# template_25x45_5V.net
KiCad netlist of a schematic drawn in EAGLE
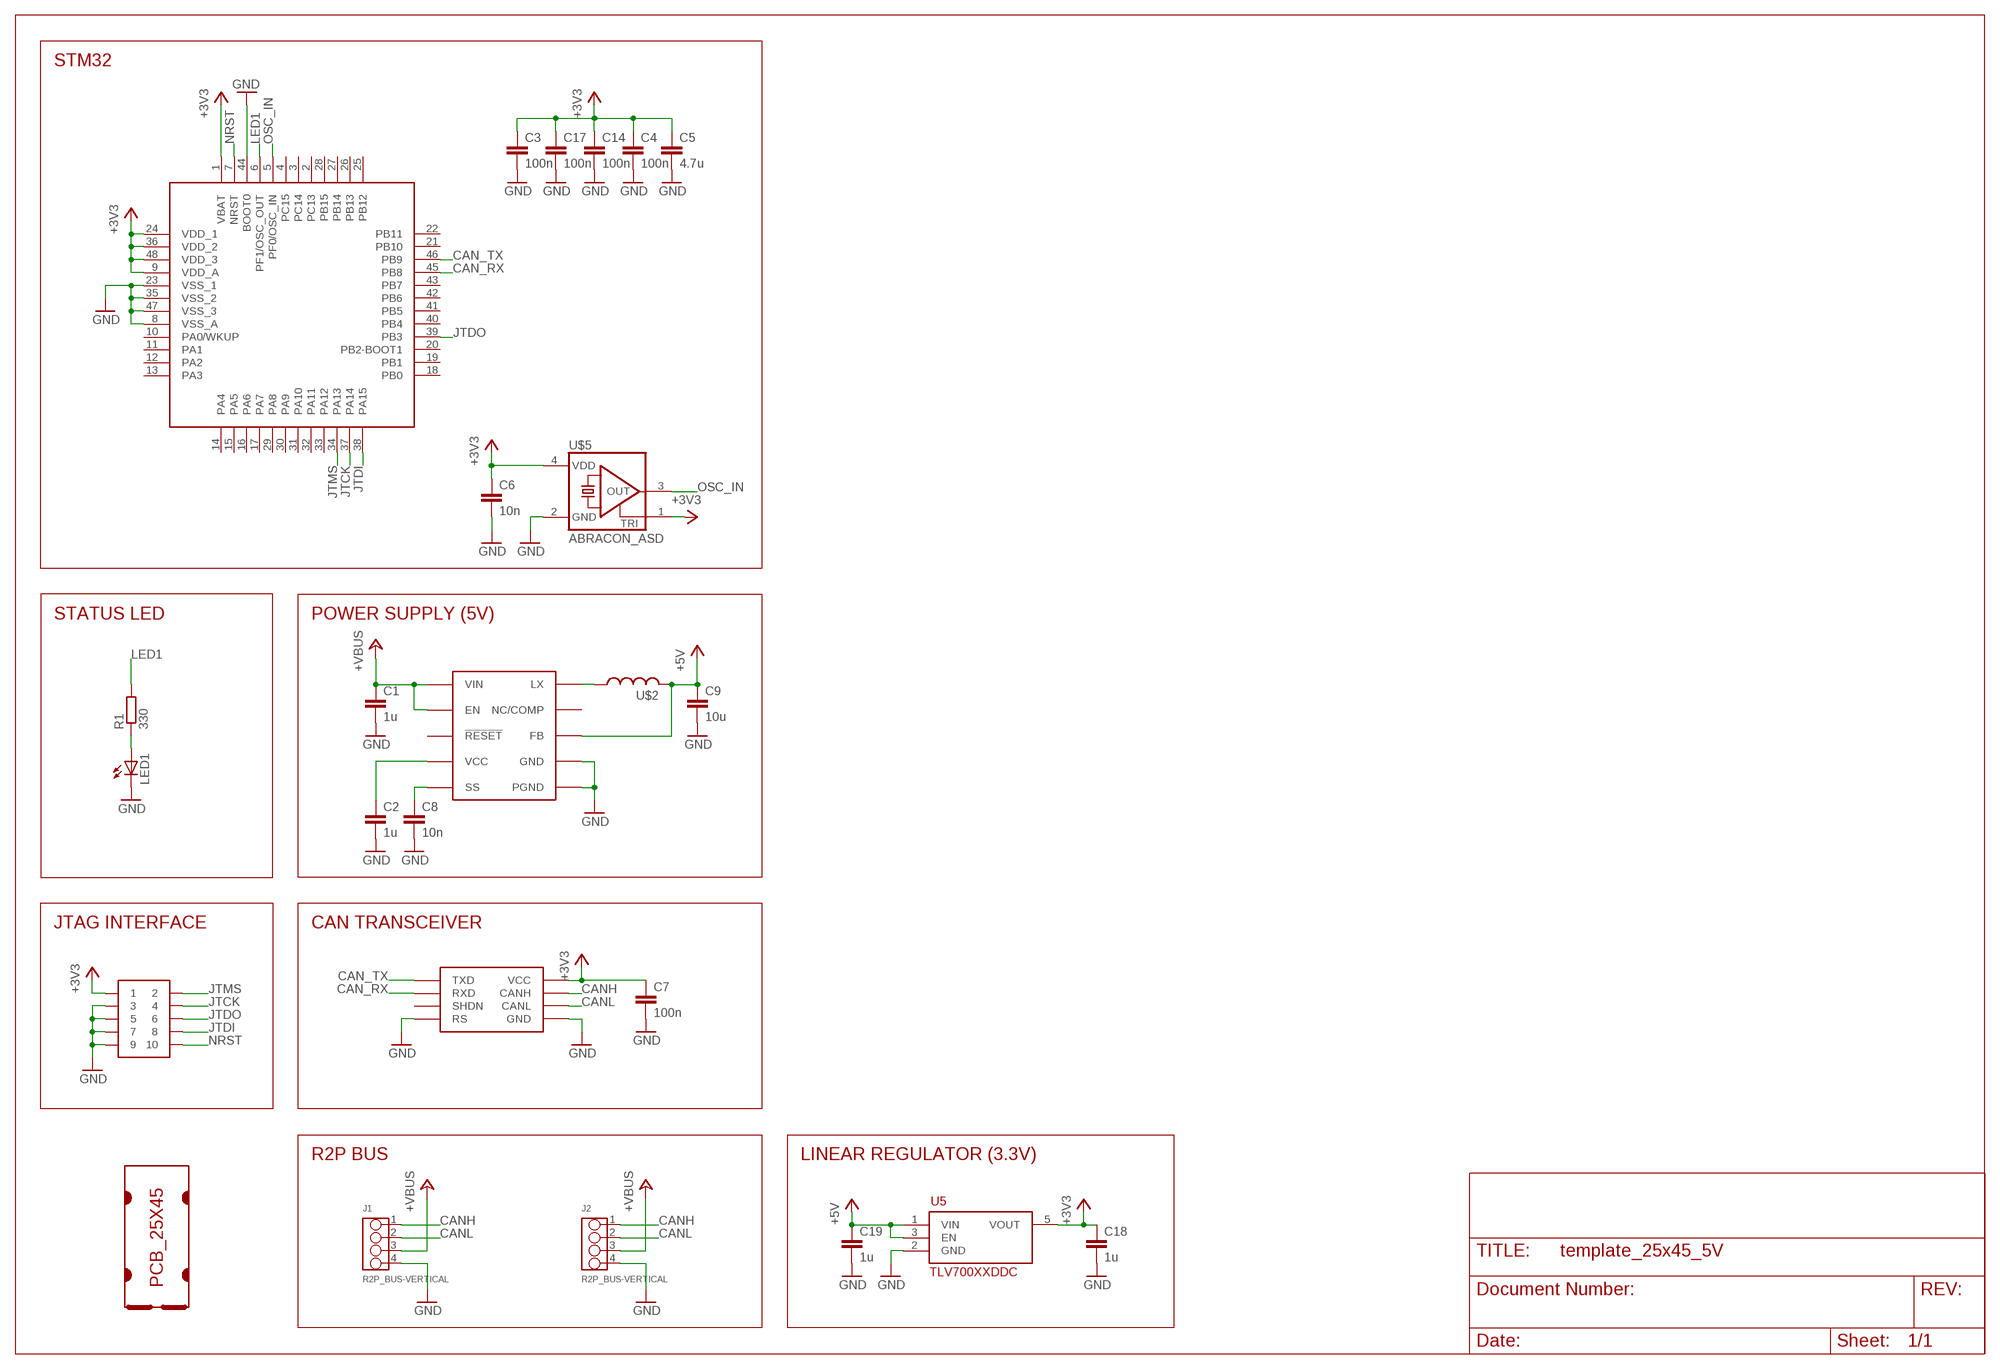
[diagram p0: schematic, sheet 1]

(export (version "E")
  (design (tool "Eeschema 10.0.6"))
  (components
    (comp (ref "C1")
      (value "1u")
      (footprint "eagle-import:C1206")
      (libsource (lib "eagle-import") (part "C1206"))
    )
    (comp (ref "C2")
      (value "1u")
      (footprint "eagle-import:C0603")
      (libsource (lib "eagle-import") (part "C0603"))
    )
    (comp (ref "C3")
      (value "100n")
      (footprint "eagle-import:C0603")
      (libsource (lib "eagle-import") (part "C0603"))
    )
    (comp (ref "C4")
      (value "100n")
      (footprint "eagle-import:C0603")
      (libsource (lib "eagle-import") (part "C0603"))
    )
    (comp (ref "C5")
      (value "4.7u")
      (footprint "eagle-import:C0805")
      (libsource (lib "eagle-import") (part "C0805"))
    )
    (comp (ref "C6")
      (value "10n")
      (footprint "eagle-import:C0603")
      (libsource (lib "eagle-import") (part "C0603"))
    )
    (comp (ref "C7")
      (value "100n")
      (footprint "eagle-import:C0603")
      (libsource (lib "eagle-import") (part "C0603"))
    )
    (comp (ref "C8")
      (value "10n")
      (footprint "eagle-import:C0603")
      (libsource (lib "eagle-import") (part "C0603"))
    )
    (comp (ref "C9")
      (value "10u")
      (footprint "eagle-import:C0805")
      (libsource (lib "eagle-import") (part "C0805"))
    )
    (comp (ref "C14")
      (value "100n")
      (footprint "eagle-import:C0603")
      (libsource (lib "eagle-import") (part "C0603"))
    )
    (comp (ref "C17")
      (value "100n")
      (footprint "eagle-import:C0603")
      (libsource (lib "eagle-import") (part "C0603"))
    )
    (comp (ref "C18")
      (value "1u")
      (footprint "eagle-import:C0603")
      (libsource (lib "eagle-import") (part "C0603"))
    )
    (comp (ref "C19")
      (value "1u")
      (footprint "eagle-import:C0603")
      (libsource (lib "eagle-import") (part "C0603"))
    )
    (comp (ref "J1")
      (value "R2P_BUS-VERTICAL")
      (footprint "eagle-import:OPL-EAGLE-LIBRARY_4P-2.0")
      (libsource (lib "eagle-import") (part "R2P_BUS-VERTICAL"))
    )
    (comp (ref "J2")
      (value "R2P_BUS-VERTICAL")
      (footprint "eagle-import:OPL-EAGLE-LIBRARY_4P-2.0")
      (libsource (lib "eagle-import") (part "R2P_BUS-VERTICAL"))
    )
    (comp (ref "LED1")
      (value "LED0805")
      (footprint "eagle-import:CHIPLED_0805")
      (libsource (lib "eagle-import") (part "LED0805"))
    )
    (comp (ref "R1")
      (value "330")
      (footprint "eagle-import:R0603")
      (libsource (lib "eagle-import") (part "R0603"))
    )
    (comp (ref "SOT1")
      (value "MAX3051EKA")
      (footprint "eagle-import:SOT23-8L")
      (libsource (lib "eagle-import") (part "MAX3051EKA"))
    )
    (comp (ref "U$1")
      (value "PCB_25X45")
      (footprint "eagle-import:25X45")
      (libsource (lib "eagle-import") (part "PCB_25X45"))
    )
    (comp (ref "U$2")
      (value "LPS4018")
      (footprint "eagle-import:COILCRAFT_LPS4018")
      (libsource (lib "eagle-import") (part "LPS4018"))
    )
    (comp (ref "U$3")
      (value "MAX17501")
      (footprint "eagle-import:TDFN-10")
      (libsource (lib "eagle-import") (part "MAX17501"))
    )
    (comp (ref "U$4")
      (value "JTAG-TH")
      (footprint "eagle-import:SAMTEC_FTSH-105-TH")
      (libsource (lib "eagle-import") (part "JTAG-TH"))
    )
    (comp (ref "U$5")
      (value "ABRACON_ASD")
      (footprint "eagle-import:ABRACON_2.5X2")
      (libsource (lib "eagle-import") (part "ABRACON_ASD"))
    )
    (comp (ref "U$6")
      (value "STM32F303CTX")
      (footprint "eagle-import:LQFP48")
      (libsource (lib "eagle-import") (part "STM32F303CTX"))
    )
    (comp (ref "U5")
      (value "TLV700XXDDC")
      (footprint "eagle-import:SOT23-5L")
      (libsource (lib "eagle-import") (part "TLV700XXDDC"))
    )
  )
  (nets
    (net (code "1") (name "+3V3") (class "Default")
      (node (ref "C14") (pin "1") (pinfunction "1_1") (pintype "passive"))
      (node (ref "C17") (pin "1") (pinfunction "1_1") (pintype "passive"))
      (node (ref "C18") (pin "1") (pinfunction "1_1") (pintype "passive"))
      (node (ref "C3") (pin "1") (pinfunction "1_1") (pintype "passive"))
      (node (ref "C4") (pin "1") (pinfunction "1_1") (pintype "passive"))
      (node (ref "C5") (pin "1") (pinfunction "1_1") (pintype "passive"))
      (node (ref "C6") (pin "1") (pinfunction "1_1") (pintype "passive"))
      (node (ref "C7") (pin "1") (pinfunction "1_1") (pintype "passive"))
      (node (ref "SOT1") (pin "3") (pinfunction "VCC_3") (pintype "bidirectional"))
      (node (ref "U$4") (pin "1") (pinfunction "1_1") (pintype "bidirectional"))
      (node (ref "U$5") (pin "1") (pinfunction "TRI_1") (pintype "input"))
      (node (ref "U$5") (pin "4") (pinfunction "VDD_4") (pintype "power_in"))
      (node (ref "U$6") (pin "1") (pinfunction "VBAT_1") (pintype "bidirectional"))
      (node (ref "U$6") (pin "24") (pinfunction "VDD_1_24") (pintype "bidirectional"))
      (node (ref "U$6") (pin "36") (pinfunction "VDD_2_36") (pintype "bidirectional"))
      (node (ref "U$6") (pin "48") (pinfunction "VDD_3_48") (pintype "bidirectional"))
      (node (ref "U$6") (pin "9") (pinfunction "VDD_A_9") (pintype "bidirectional"))
      (node (ref "U5") (pin "5") (pinfunction "VOUT_5") (pintype "bidirectional"))
    )
    (net (code "2") (name "+5V") (class "Default")
      (node (ref "C19") (pin "1") (pinfunction "1_1") (pintype "passive"))
      (node (ref "C9") (pin "1") (pinfunction "1_1") (pintype "passive"))
      (node (ref "U$2") (pin "P$2") (pinfunction "2_P$2") (pintype "passive"))
      (node (ref "U$3") (pin "P$5") (pinfunction "FB_P$5") (pintype "bidirectional"))
      (node (ref "U5") (pin "1") (pinfunction "VIN_1") (pintype "bidirectional"))
      (node (ref "U5") (pin "3") (pinfunction "EN_3") (pintype "bidirectional"))
    )
    (net (code "3") (name "+VBUS") (class "Default")
      (node (ref "C1") (pin "1") (pinfunction "1_1") (pintype "passive"))
      (node (ref "J1") (pin "3") (pinfunction "3_3") (pintype "bidirectional"))
      (node (ref "J2") (pin "3") (pinfunction "3_3") (pintype "bidirectional"))
      (node (ref "U$3") (pin "P$2") (pinfunction "VIN_P$2") (pintype "bidirectional"))
      (node (ref "U$3") (pin "P$3") (pinfunction "EN_P$3") (pintype "bidirectional"))
    )
    (net (code "4") (name "/CANH") (class "Default")
      (node (ref "J1") (pin "1") (pinfunction "1_1") (pintype "bidirectional"))
      (node (ref "J2") (pin "1") (pinfunction "1_1") (pintype "bidirectional"))
      (node (ref "SOT1") (pin "7") (pinfunction "CANH_7") (pintype "bidirectional"))
    )
    (net (code "5") (name "/CANL") (class "Default")
      (node (ref "J1") (pin "2") (pinfunction "2_2") (pintype "bidirectional"))
      (node (ref "J2") (pin "2") (pinfunction "2_2") (pintype "bidirectional"))
      (node (ref "SOT1") (pin "6") (pinfunction "CANL_6") (pintype "bidirectional"))
    )
    (net (code "6") (name "/CAN_RX") (class "Default")
      (node (ref "SOT1") (pin "4") (pinfunction "RXD_4") (pintype "bidirectional"))
      (node (ref "U$6") (pin "45") (pinfunction "PB8_45") (pintype "bidirectional"))
    )
    (net (code "7") (name "/CAN_TX") (class "Default")
      (node (ref "SOT1") (pin "1") (pinfunction "TXD_1") (pintype "bidirectional"))
      (node (ref "U$6") (pin "46") (pinfunction "PB9_46") (pintype "bidirectional"))
    )
    (net (code "8") (name "/JTCK") (class "Default")
      (node (ref "U$4") (pin "4") (pinfunction "4_4") (pintype "bidirectional"))
      (node (ref "U$6") (pin "37") (pinfunction "PA14_37") (pintype "bidirectional"))
    )
    (net (code "9") (name "/JTDI") (class "Default")
      (node (ref "U$4") (pin "8") (pinfunction "8_8") (pintype "bidirectional"))
      (node (ref "U$6") (pin "38") (pinfunction "PA15_38") (pintype "bidirectional"))
    )
    (net (code "10") (name "/JTDO") (class "Default")
      (node (ref "U$4") (pin "6") (pinfunction "6_6") (pintype "bidirectional"))
      (node (ref "U$6") (pin "39") (pinfunction "PB3_39") (pintype "bidirectional"))
    )
    (net (code "11") (name "/JTMS") (class "Default")
      (node (ref "U$4") (pin "2") (pinfunction "2_2") (pintype "bidirectional"))
      (node (ref "U$6") (pin "34") (pinfunction "PA13_34") (pintype "bidirectional"))
    )
    (net (code "12") (name "/LED1") (class "Default")
      (node (ref "R1") (pin "2") (pinfunction "2_2") (pintype "passive"))
      (node (ref "U$6") (pin "6") (pinfunction "PF1/OSC_OUT_6") (pintype "bidirectional"))
    )
    (net (code "13") (name "/NRST") (class "Default")
      (node (ref "U$4") (pin "10") (pinfunction "10_10") (pintype "bidirectional"))
      (node (ref "U$6") (pin "7") (pinfunction "NRST_7") (pintype "bidirectional"))
    )
    (net (code "14") (name "/OSC_IN") (class "Default")
      (node (ref "U$5") (pin "3") (pinfunction "OUT_3") (pintype "output"))
      (node (ref "U$6") (pin "5") (pinfunction "PF0/OSC_IN_5") (pintype "bidirectional"))
    )
    (net (code "15") (name "GND") (class "Default")
      (node (ref "C1") (pin "2") (pinfunction "2_2") (pintype "passive"))
      (node (ref "C14") (pin "2") (pinfunction "2_2") (pintype "passive"))
      (node (ref "C17") (pin "2") (pinfunction "2_2") (pintype "passive"))
      (node (ref "C18") (pin "2") (pinfunction "2_2") (pintype "passive"))
      (node (ref "C19") (pin "2") (pinfunction "2_2") (pintype "passive"))
      (node (ref "C2") (pin "2") (pinfunction "2_2") (pintype "passive"))
      (node (ref "C3") (pin "2") (pinfunction "2_2") (pintype "passive"))
      (node (ref "C4") (pin "2") (pinfunction "2_2") (pintype "passive"))
      (node (ref "C5") (pin "2") (pinfunction "2_2") (pintype "passive"))
      (node (ref "C6") (pin "2") (pinfunction "2_2") (pintype "passive"))
      (node (ref "C7") (pin "2") (pinfunction "2_2") (pintype "passive"))
      (node (ref "C8") (pin "2") (pinfunction "2_2") (pintype "passive"))
      (node (ref "C9") (pin "2") (pinfunction "2_2") (pintype "passive"))
      (node (ref "J1") (pin "4") (pinfunction "4_4") (pintype "bidirectional"))
      (node (ref "J2") (pin "4") (pinfunction "4_4") (pintype "bidirectional"))
      (node (ref "LED1") (pin "C") (pinfunction "C_C") (pintype "passive"))
      (node (ref "SOT1") (pin "2") (pinfunction "GND_2") (pintype "bidirectional"))
      (node (ref "SOT1") (pin "8") (pinfunction "RS_8") (pintype "bidirectional"))
      (node (ref "U$3") (pin "P$1") (pinfunction "PGND_P$1") (pintype "bidirectional"))
      (node (ref "U$3") (pin "P$11") (pinfunction "PGND_P$11") (pintype "bidirectional"))
      (node (ref "U$3") (pin "P$9") (pinfunction "GND_P$9") (pintype "bidirectional"))
      (node (ref "U$4") (pin "3") (pinfunction "3_3") (pintype "bidirectional"))
      (node (ref "U$4") (pin "5") (pinfunction "5_5") (pintype "bidirectional"))
      (node (ref "U$4") (pin "7") (pinfunction "7_7") (pintype "bidirectional"))
      (node (ref "U$4") (pin "9") (pinfunction "9_9") (pintype "bidirectional"))
      (node (ref "U$5") (pin "2") (pinfunction "GND_2") (pintype "power_in"))
      (node (ref "U$6") (pin "23") (pinfunction "VSS_1_23") (pintype "bidirectional"))
      (node (ref "U$6") (pin "35") (pinfunction "VSS_2_35") (pintype "bidirectional"))
      (node (ref "U$6") (pin "44") (pinfunction "BOOT0_44") (pintype "bidirectional"))
      (node (ref "U$6") (pin "47") (pinfunction "VSS_3_47") (pintype "bidirectional"))
      (node (ref "U$6") (pin "8") (pinfunction "VSS_A_8") (pintype "bidirectional"))
      (node (ref "U5") (pin "2") (pinfunction "GND_2") (pintype "bidirectional"))
    )
    (net (code "16") (name "Net-(LED1-PadA)") (class "Default")
      (node (ref "LED1") (pin "A") (pinfunction "A_A") (pintype "passive"))
      (node (ref "R1") (pin "1") (pinfunction "1_1") (pintype "passive"))
    )
    (net (code "17") (name "Net-(U$2-1)") (class "Default")
      (node (ref "U$2") (pin "P$1") (pinfunction "1_P$1") (pintype "passive"))
      (node (ref "U$3") (pin "P$10") (pinfunction "LX_P$10") (pintype "bidirectional"))
    )
    (net (code "18") (name "Net-(U$3-SS)") (class "Default")
      (node (ref "C8") (pin "1") (pinfunction "1_1") (pintype "passive"))
      (node (ref "U$3") (pin "P$6") (pinfunction "SS_P$6") (pintype "bidirectional"))
    )
    (net (code "19") (name "Net-(U$3-VCC)") (class "Default")
      (node (ref "C2") (pin "1") (pinfunction "1_1") (pintype "passive"))
      (node (ref "U$3") (pin "P$4") (pinfunction "VCC_P$4") (pintype "bidirectional"))
    )
    (net (code "20") (name "unconnected-(SOT1-SHDN-Pad5)") (class "Default")
      (node (ref "SOT1") (pin "5") (pinfunction "SHDN_5") (pintype "bidirectional"))
    )
    (net (code "21") (name "unconnected-(U$3-NC{slash}COMP-PadP$7)") (class "Default")
      (node (ref "U$3") (pin "P$7") (pinfunction "NC/COMP_P$7") (pintype "bidirectional"))
    )
    (net (code "22") (name "unconnected-(U$3-~{RESET}-PadP$8)") (class "Default")
      (node (ref "U$3") (pin "P$8") (pinfunction "~{RESET}_P$8") (pintype "bidirectional"))
    )
    (net (code "23") (name "unconnected-(U$6-PA0{slash}WKUP-Pad10)") (class "Default")
      (node (ref "U$6") (pin "10") (pinfunction "PA0/WKUP_10") (pintype "bidirectional"))
    )
    (net (code "24") (name "unconnected-(U$6-PA1-Pad11)") (class "Default")
      (node (ref "U$6") (pin "11") (pinfunction "PA1_11") (pintype "bidirectional"))
    )
    (net (code "25") (name "unconnected-(U$6-PA2-Pad12)") (class "Default")
      (node (ref "U$6") (pin "12") (pinfunction "PA2_12") (pintype "bidirectional"))
    )
    (net (code "26") (name "unconnected-(U$6-PA3-Pad13)") (class "Default")
      (node (ref "U$6") (pin "13") (pinfunction "PA3_13") (pintype "bidirectional"))
    )
    (net (code "27") (name "unconnected-(U$6-PA4-Pad14)") (class "Default")
      (node (ref "U$6") (pin "14") (pinfunction "PA4_14") (pintype "bidirectional"))
    )
    (net (code "28") (name "unconnected-(U$6-PA5-Pad15)") (class "Default")
      (node (ref "U$6") (pin "15") (pinfunction "PA5_15") (pintype "bidirectional"))
    )
    (net (code "29") (name "unconnected-(U$6-PA6-Pad16)") (class "Default")
      (node (ref "U$6") (pin "16") (pinfunction "PA6_16") (pintype "bidirectional"))
    )
    (net (code "30") (name "unconnected-(U$6-PA7-Pad17)") (class "Default")
      (node (ref "U$6") (pin "17") (pinfunction "PA7_17") (pintype "bidirectional"))
    )
    (net (code "31") (name "unconnected-(U$6-PA8-Pad29)") (class "Default")
      (node (ref "U$6") (pin "29") (pinfunction "PA8_29") (pintype "bidirectional"))
    )
    (net (code "32") (name "unconnected-(U$6-PA9-Pad30)") (class "Default")
      (node (ref "U$6") (pin "30") (pinfunction "PA9_30") (pintype "bidirectional"))
    )
    (net (code "33") (name "unconnected-(U$6-PA10-Pad31)") (class "Default")
      (node (ref "U$6") (pin "31") (pinfunction "PA10_31") (pintype "bidirectional"))
    )
    (net (code "34") (name "unconnected-(U$6-PA11-Pad32)") (class "Default")
      (node (ref "U$6") (pin "32") (pinfunction "PA11_32") (pintype "bidirectional"))
    )
    (net (code "35") (name "unconnected-(U$6-PA12-Pad33)") (class "Default")
      (node (ref "U$6") (pin "33") (pinfunction "PA12_33") (pintype "bidirectional"))
    )
    (net (code "36") (name "unconnected-(U$6-PB0-Pad18)") (class "Default")
      (node (ref "U$6") (pin "18") (pinfunction "PB0_18") (pintype "bidirectional"))
    )
    (net (code "37") (name "unconnected-(U$6-PB1-Pad19)") (class "Default")
      (node (ref "U$6") (pin "19") (pinfunction "PB1_19") (pintype "bidirectional"))
    )
    (net (code "38") (name "unconnected-(U$6-PB2-BOOT1-Pad20)") (class "Default")
      (node (ref "U$6") (pin "20") (pinfunction "PB2-BOOT1_20") (pintype "bidirectional"))
    )
    (net (code "39") (name "unconnected-(U$6-PB4-Pad40)") (class "Default")
      (node (ref "U$6") (pin "40") (pinfunction "PB4_40") (pintype "bidirectional"))
    )
    (net (code "40") (name "unconnected-(U$6-PB5-Pad41)") (class "Default")
      (node (ref "U$6") (pin "41") (pinfunction "PB5_41") (pintype "bidirectional"))
    )
    (net (code "41") (name "unconnected-(U$6-PB6-Pad42)") (class "Default")
      (node (ref "U$6") (pin "42") (pinfunction "PB6_42") (pintype "bidirectional"))
    )
    (net (code "42") (name "unconnected-(U$6-PB7-Pad43)") (class "Default")
      (node (ref "U$6") (pin "43") (pinfunction "PB7_43") (pintype "bidirectional"))
    )
    (net (code "43") (name "unconnected-(U$6-PB10-Pad21)") (class "Default")
      (node (ref "U$6") (pin "21") (pinfunction "PB10_21") (pintype "bidirectional"))
    )
    (net (code "44") (name "unconnected-(U$6-PB11-Pad22)") (class "Default")
      (node (ref "U$6") (pin "22") (pinfunction "PB11_22") (pintype "bidirectional"))
    )
    (net (code "45") (name "unconnected-(U$6-PB12-Pad25)") (class "Default")
      (node (ref "U$6") (pin "25") (pinfunction "PB12_25") (pintype "bidirectional"))
    )
    (net (code "46") (name "unconnected-(U$6-PB13-Pad26)") (class "Default")
      (node (ref "U$6") (pin "26") (pinfunction "PB13_26") (pintype "bidirectional"))
    )
    (net (code "47") (name "unconnected-(U$6-PB14-Pad27)") (class "Default")
      (node (ref "U$6") (pin "27") (pinfunction "PB14_27") (pintype "bidirectional"))
    )
    (net (code "48") (name "unconnected-(U$6-PB15-Pad28)") (class "Default")
      (node (ref "U$6") (pin "28") (pinfunction "PB15_28") (pintype "bidirectional"))
    )
    (net (code "49") (name "unconnected-(U$6-PC13-Pad2)") (class "Default")
      (node (ref "U$6") (pin "2") (pinfunction "PC13_2") (pintype "bidirectional"))
    )
    (net (code "50") (name "unconnected-(U$6-PC14-Pad3)") (class "Default")
      (node (ref "U$6") (pin "3") (pinfunction "PC14_3") (pintype "bidirectional"))
    )
    (net (code "51") (name "unconnected-(U$6-PC15-Pad4)") (class "Default")
      (node (ref "U$6") (pin "4") (pinfunction "PC15_4") (pintype "bidirectional"))
    )
  )
)
